# SB_TS_1_54.net
KiCad netlist of a schematic drawn in EAGLE
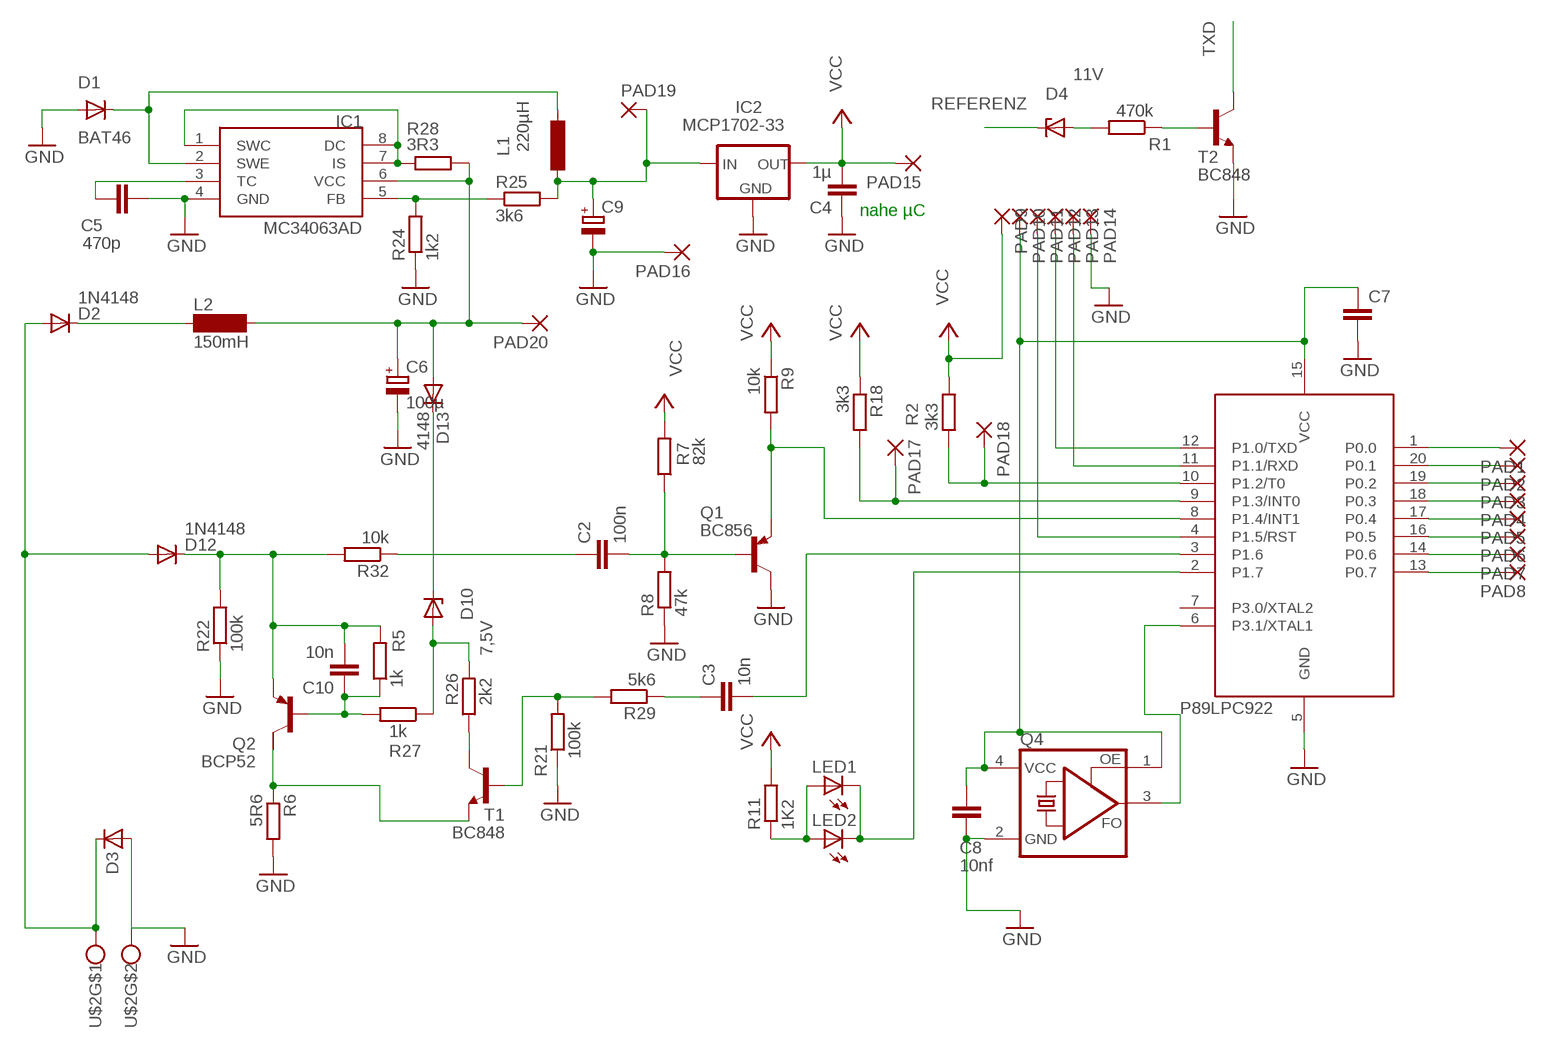
[diagram p0: schematic, sheet 1]

(export (version "E")
  (design (tool "Eeschema 10.0.6"))
  (components
    (comp (ref "C2")
      (value "100n")
      (footprint "eagle-import:C1206")
      (libsource (lib "eagle-import") (part "C-EUC1206"))
    )
    (comp (ref "C3")
      (value "10n")
      (footprint "eagle-import:C1206")
      (libsource (lib "eagle-import") (part "C-EUC1206"))
    )
    (comp (ref "C4")
      (value "1µ")
      (footprint "eagle-import:C1206")
      (libsource (lib "eagle-import") (part "C-EUC1206"))
    )
    (comp (ref "C5")
      (value "470p")
      (footprint "eagle-import:C1206")
      (libsource (lib "eagle-import") (part "C-EUC1206"))
    )
    (comp (ref "C6")
      (value "100µ")
      (footprint "eagle-import:SANYO-OSCON_SMD_C6")
      (libsource (lib "eagle-import") (part "CPOL-EUSANYO_SMD_C6"))
    )
    (comp (ref "C7")
      (value "C-EUC1206")
      (footprint "eagle-import:C1206")
      (libsource (lib "eagle-import") (part "C-EUC1206"))
    )
    (comp (ref "C8")
      (value "10nf")
      (footprint "eagle-import:C1206")
      (libsource (lib "eagle-import") (part "C-EUC1206"))
    )
    (comp (ref "C9")
      (value "CPOL-EUE2.5-5")
      (footprint "eagle-import:E2,5-5")
      (libsource (lib "eagle-import") (part "CPOL-EUE2.5-5"))
    )
    (comp (ref "C10")
      (value "10n")
      (footprint "eagle-import:C1206")
      (libsource (lib "eagle-import") (part "C-EUC1206"))
    )
    (comp (ref "D1")
      (value "BAT46")
      (footprint "eagle-import:MINIMELF")
      (libsource (lib "eagle-import") (part "DIODE-MINIMELF"))
    )
    (comp (ref "D2")
      (value "1N4148")
      (footprint "eagle-import:MINIMELF")
      (libsource (lib "eagle-import") (part "DIODE-MINIMELF"))
    )
    (comp (ref "D3")
      (value "SMAJ40AC")
      (footprint "eagle-import:SMB")
      (libsource (lib "eagle-import") (part "D-SMB"))
    )
    (comp (ref "D4")
      (value "11V")
      (footprint "eagle-import:MINIMELF")
      (libsource (lib "eagle-import") (part "ZPD"))
    )
    (comp (ref "D10")
      (value "7,5V")
      (footprint "eagle-import:MINIMELF")
      (libsource (lib "eagle-import") (part "ZPD"))
    )
    (comp (ref "D12")
      (value "1N4148")
      (footprint "eagle-import:MINIMELF")
      (libsource (lib "eagle-import") (part "DIODE-MINIMELF"))
    )
    (comp (ref "D13")
      (value "4148")
      (footprint "eagle-import:MINIMELF")
      (libsource (lib "eagle-import") (part "DIODE-MINIMELF"))
    )
    (comp (ref "IC1")
      (value "MC34063AD")
      (footprint "eagle-import:SOIC8")
      (libsource (lib "eagle-import") (part "MC34063AD"))
    )
    (comp (ref "IC2")
      (value "MCP1702-33")
      (footprint "eagle-import:79LXX")
      (libsource (lib "eagle-import") (part "79LXX"))
    )
    (comp (ref "L1")
      (value "220µH")
      (footprint "eagle-import:2200-11.43")
      (libsource (lib "eagle-import") (part "L-EU2200-11.43"))
    )
    (comp (ref "L2")
      (value "150mH")
      (footprint "eagle-import:SD12_1000")
      (libsource (lib "eagle-import") (part "SD12-1000"))
    )
    (comp (ref "LED1")
      (value "LEDCHIPLED_1206")
      (footprint "eagle-import:CHIPLED_1206")
      (libsource (lib "eagle-import") (part "LEDCHIPLED_1206"))
    )
    (comp (ref "LED2")
      (value "LED3MM")
      (footprint "eagle-import:LED3MM")
      (libsource (lib "eagle-import") (part "LED3MM"))
    )
    (comp (ref "PAD1")
      (value "SMD2")
      (footprint "eagle-import:SMD1,27-2,54")
      (libsource (lib "eagle-import") (part "SMD2"))
    )
    (comp (ref "PAD2")
      (value "SMD2")
      (footprint "eagle-import:SMD1,27-2,54")
      (libsource (lib "eagle-import") (part "SMD2"))
    )
    (comp (ref "PAD3")
      (value "SMD2")
      (footprint "eagle-import:SMD1,27-2,54")
      (libsource (lib "eagle-import") (part "SMD2"))
    )
    (comp (ref "PAD4")
      (value "SMD2")
      (footprint "eagle-import:SMD1,27-2,54")
      (libsource (lib "eagle-import") (part "SMD2"))
    )
    (comp (ref "PAD5")
      (value "SMD2")
      (footprint "eagle-import:SMD1,27-2,54")
      (libsource (lib "eagle-import") (part "SMD2"))
    )
    (comp (ref "PAD6")
      (value "SMD2")
      (footprint "eagle-import:SMD1,27-2,54")
      (libsource (lib "eagle-import") (part "SMD2"))
    )
    (comp (ref "PAD7")
      (value "SMD2")
      (footprint "eagle-import:SMD1,27-2,54")
      (libsource (lib "eagle-import") (part "SMD2"))
    )
    (comp (ref "PAD8")
      (value "SMD2")
      (footprint "eagle-import:SMD1,27-2,54")
      (libsource (lib "eagle-import") (part "SMD2"))
    )
    (comp (ref "PAD9")
      (value "SMD2")
      (footprint "eagle-import:SMD1,27-2,54")
      (libsource (lib "eagle-import") (part "SMD2"))
    )
    (comp (ref "PAD10")
      (value "SMD2")
      (footprint "eagle-import:SMD1,27-2,54")
      (libsource (lib "eagle-import") (part "SMD2"))
    )
    (comp (ref "PAD11")
      (value "SMD2")
      (footprint "eagle-import:SMD1,27-2,54")
      (libsource (lib "eagle-import") (part "SMD2"))
    )
    (comp (ref "PAD12")
      (value "SMD2")
      (footprint "eagle-import:SMD1,27-2,54")
      (libsource (lib "eagle-import") (part "SMD2"))
    )
    (comp (ref "PAD13")
      (value "SMD2")
      (footprint "eagle-import:SMD1,27-2,54")
      (libsource (lib "eagle-import") (part "SMD2"))
    )
    (comp (ref "PAD14")
      (value "SMD2")
      (footprint "eagle-import:SMD1,27-2,54")
      (libsource (lib "eagle-import") (part "SMD2"))
    )
    (comp (ref "PAD15")
      (value "SMD2")
      (footprint "eagle-import:SMD1,27-2,54")
      (libsource (lib "eagle-import") (part "SMD2"))
    )
    (comp (ref "PAD16")
      (value "SMD2")
      (footprint "eagle-import:SMD1,27-2,54")
      (libsource (lib "eagle-import") (part "SMD2"))
    )
    (comp (ref "PAD17")
      (value "SMD2")
      (footprint "eagle-import:SMD1,27-2,54")
      (libsource (lib "eagle-import") (part "SMD2"))
    )
    (comp (ref "PAD18")
      (value "SMD2")
      (footprint "eagle-import:SMD1,27-2,54")
      (libsource (lib "eagle-import") (part "SMD2"))
    )
    (comp (ref "PAD19")
      (value "SMD2")
      (footprint "eagle-import:SMD1,27-2,54")
      (libsource (lib "eagle-import") (part "SMD2"))
    )
    (comp (ref "PAD20")
      (value "SMD2")
      (footprint "eagle-import:SMD1,27-2,54")
      (libsource (lib "eagle-import") (part "SMD2"))
    )
    (comp (ref "Q1")
      (value "BC856")
      (footprint "eagle-import:SOT23-BEC")
      (libsource (lib "eagle-import") (part "BC856SMDALT1"))
    )
    (comp (ref "Q2")
      (value "BCP52")
      (footprint "eagle-import:SOT223")
      (libsource (lib "eagle-import") (part "FZT753SMD"))
    )
    (comp (ref "Q4")
      (value "ASFL")
      (footprint "eagle-import:ASF")
      (libsource (lib "eagle-import") (part "ASFL"))
    )
    (comp (ref "R1")
      (value "470k")
      (footprint "eagle-import:R1206")
      (libsource (lib "eagle-import") (part "R-EU_R1206"))
    )
    (comp (ref "R2")
      (value "3k3")
      (footprint "eagle-import:M1206")
      (libsource (lib "eagle-import") (part "R-EU_M1206"))
    )
    (comp (ref "R5")
      (value "1k")
      (footprint "eagle-import:R1206")
      (libsource (lib "eagle-import") (part "R-EU_R1206"))
    )
    (comp (ref "R6")
      (value "5R6")
      (footprint "eagle-import:R1206")
      (libsource (lib "eagle-import") (part "R-EU_R1206"))
    )
    (comp (ref "R7")
      (value "82k")
      (footprint "eagle-import:R1206")
      (libsource (lib "eagle-import") (part "R-EU_R1206"))
    )
    (comp (ref "R8")
      (value "47k")
      (footprint "eagle-import:M1206")
      (libsource (lib "eagle-import") (part "R-EU_M1206"))
    )
    (comp (ref "R9")
      (value "10k")
      (footprint "eagle-import:R1206")
      (libsource (lib "eagle-import") (part "R-EU_R1206"))
    )
    (comp (ref "R11")
      (value "1K2")
      (footprint "eagle-import:R1206")
      (libsource (lib "eagle-import") (part "R-EU_R1206"))
    )
    (comp (ref "R18")
      (value "3k3")
      (footprint "eagle-import:R1206")
      (libsource (lib "eagle-import") (part "R-EU_R1206"))
    )
    (comp (ref "R21")
      (value "100k")
      (footprint "eagle-import:R1206")
      (libsource (lib "eagle-import") (part "R-EU_R1206"))
    )
    (comp (ref "R22")
      (value "100k")
      (footprint "eagle-import:M1206")
      (libsource (lib "eagle-import") (part "R-EU_M1206"))
    )
    (comp (ref "R24")
      (value "1k2")
      (footprint "eagle-import:R1206")
      (libsource (lib "eagle-import") (part "R-EU_R1206"))
    )
    (comp (ref "R25")
      (value "3k6")
      (footprint "eagle-import:M1206")
      (libsource (lib "eagle-import") (part "R-EU_M1206"))
    )
    (comp (ref "R26")
      (value "2k2")
      (footprint "eagle-import:M1206")
      (libsource (lib "eagle-import") (part "R-EU_M1206"))
    )
    (comp (ref "R27")
      (value "1k")
      (footprint "eagle-import:R1206")
      (libsource (lib "eagle-import") (part "R-EU_R1206"))
    )
    (comp (ref "R28")
      (value "3R3")
      (footprint "eagle-import:M1206")
      (libsource (lib "eagle-import") (part "R-EU_M1206"))
    )
    (comp (ref "R29")
      (value "5k6")
      (footprint "eagle-import:R1206")
      (libsource (lib "eagle-import") (part "R-EU_R1206"))
    )
    (comp (ref "R32")
      (value "10k")
      (footprint "eagle-import:R1206")
      (libsource (lib "eagle-import") (part "R-EU_R1206"))
    )
    (comp (ref "T1")
      (value "BC848")
      (footprint "eagle-import:SOT23")
      (libsource (lib "eagle-import") (part "BC848"))
    )
    (comp (ref "T2")
      (value "BC848")
      (footprint "eagle-import:SOT23")
      (libsource (lib "eagle-import") (part "BC848"))
    )
    (comp (ref "U$2")
      (value "AKL059-02")
      (footprint "eagle-import:AKL3.5X2")
      (libsource (lib "eagle-import") (part "AKL059-02"))
    )
    (comp (ref "U1")
      (value "89LPC922")
      (footprint "eagle-import:DIL20")
      (libsource (lib "eagle-import") (part "89LPC922"))
    )
  )
  (nets
    (net (code "1") (name "/REFERENZ") (class "Default")
      (node (ref "D10") (pin "A") (pinfunction "A_A") (pintype "passive"))
      (node (ref "D4") (pin "C") (pinfunction "C_C") (pintype "passive"))
      (node (ref "R26") (pin "2") (pinfunction "2_2") (pintype "passive"))
      (node (ref "R27") (pin "1") (pinfunction "1_1") (pintype "passive"))
    )
    (net (code "2") (name "/TXD") (class "Default")
      (node (ref "PAD12") (pin "1") (pinfunction "P_1") (pintype "passive"))
      (node (ref "T2") (pin "3") (pinfunction "C_3") (pintype "passive"))
      (node (ref "U1") (pin "12") (pinfunction "P1.0/TXD_12") (pintype "bidirectional"))
    )
    (net (code "3") (name "GND") (class "Default")
      (node (ref "C4") (pin "1") (pinfunction "1_1") (pintype "passive"))
      (node (ref "C5") (pin "2") (pinfunction "2_2") (pintype "passive"))
      (node (ref "C6") (pin "-") (pinfunction "-_-") (pintype "passive"))
      (node (ref "C7") (pin "2") (pinfunction "2_2") (pintype "passive"))
      (node (ref "C8") (pin "2") (pinfunction "2_2") (pintype "passive"))
      (node (ref "C9") (pin "-") (pinfunction "-_-") (pintype "passive"))
      (node (ref "D1") (pin "A") (pinfunction "A_A") (pintype "passive"))
      (node (ref "D3") (pin "2") (pinfunction "A_2") (pintype "passive"))
      (node (ref "IC1") (pin "4") (pinfunction "GND_4") (pintype "passive"))
      (node (ref "IC2") (pin "GND") (pinfunction "GND_GND") (pintype "input"))
      (node (ref "PAD14") (pin "1") (pinfunction "P_1") (pintype "passive"))
      (node (ref "PAD16") (pin "1") (pinfunction "P_1") (pintype "passive"))
      (node (ref "Q1") (pin "C") (pinfunction "C_C") (pintype "passive"))
      (node (ref "Q4") (pin "2") (pinfunction "GND_2") (pintype "power_in"))
      (node (ref "R21") (pin "1") (pinfunction "1_1") (pintype "passive"))
      (node (ref "R22") (pin "1") (pinfunction "1_1") (pintype "passive"))
      (node (ref "R24") (pin "1") (pinfunction "1_1") (pintype "passive"))
      (node (ref "R6") (pin "2") (pinfunction "2_2") (pintype "passive"))
      (node (ref "R8") (pin "1") (pinfunction "1_1") (pintype "passive"))
      (node (ref "T2") (pin "2") (pinfunction "E_2") (pintype "passive"))
      (node (ref "U$2") (pin "2") (pinfunction "KL_2") (pintype "passive"))
      (node (ref "U1") (pin "5") (pinfunction "GND_5") (pintype "bidirectional"))
    )
    (net (code "4") (name "Net-(C2-Pad1)") (class "Default")
      (node (ref "C2") (pin "1") (pinfunction "1_1") (pintype "passive"))
      (node (ref "R32") (pin "1") (pinfunction "1_1") (pintype "passive"))
    )
    (net (code "5") (name "Net-(C2-Pad2)") (class "Default")
      (node (ref "C2") (pin "2") (pinfunction "2_2") (pintype "passive"))
      (node (ref "Q1") (pin "B") (pinfunction "B_B") (pintype "passive"))
      (node (ref "R7") (pin "1") (pinfunction "1_1") (pintype "passive"))
      (node (ref "R8") (pin "2") (pinfunction "2_2") (pintype "passive"))
    )
    (net (code "6") (name "Net-(C3-Pad1)") (class "Default")
      (node (ref "C3") (pin "1") (pinfunction "1_1") (pintype "passive"))
      (node (ref "R29") (pin "1") (pinfunction "1_1") (pintype "passive"))
    )
    (net (code "7") (name "Net-(D2-PadC)") (class "Default")
      (node (ref "D2") (pin "C") (pinfunction "C_C") (pintype "passive"))
      (node (ref "L2") (pin "1") (pinfunction "1_1") (pintype "passive"))
    )
    (net (code "8") (name "Net-(D3-C)") (class "Default")
      (node (ref "D12") (pin "A") (pinfunction "A_A") (pintype "passive"))
      (node (ref "D2") (pin "A") (pinfunction "A_A") (pintype "passive"))
      (node (ref "D3") (pin "1") (pinfunction "C_1") (pintype "passive"))
      (node (ref "U$2") (pin "1") (pinfunction "KL_1") (pintype "passive"))
    )
    (net (code "9") (name "Net-(D4-PadA)") (class "Default")
      (node (ref "D4") (pin "A") (pinfunction "A_A") (pintype "passive"))
      (node (ref "R1") (pin "2") (pinfunction "2_2") (pintype "passive"))
    )
    (net (code "10") (name "Net-(D10-PadC)") (class "Default")
      (node (ref "D10") (pin "C") (pinfunction "C_C") (pintype "passive"))
      (node (ref "D13") (pin "C") (pinfunction "C_C") (pintype "passive"))
    )
    (net (code "11") (name "Net-(IC1-DC)") (class "Default")
      (node (ref "IC1") (pin "1") (pinfunction "SWC_1") (pintype "passive"))
      (node (ref "IC1") (pin "7") (pinfunction "IS_7") (pintype "passive"))
      (node (ref "IC1") (pin "8") (pinfunction "DC_8") (pintype "passive"))
      (node (ref "R28") (pin "1") (pinfunction "1_1") (pintype "passive"))
    )
    (net (code "12") (name "Net-(IC1-FB)") (class "Default")
      (node (ref "IC1") (pin "5") (pinfunction "FB_5") (pintype "passive"))
      (node (ref "R24") (pin "2") (pinfunction "2_2") (pintype "passive"))
      (node (ref "R25") (pin "1") (pinfunction "1_1") (pintype "passive"))
    )
    (net (code "13") (name "Net-(IC1-SWE)") (class "Default")
      (node (ref "D1") (pin "C") (pinfunction "C_C") (pintype "passive"))
      (node (ref "IC1") (pin "2") (pinfunction "SWE_2") (pintype "passive"))
      (node (ref "L1") (pin "2") (pinfunction "2_2") (pintype "passive"))
    )
    (net (code "14") (name "Net-(IC1-TC)") (class "Default")
      (node (ref "C5") (pin "1") (pinfunction "1_1") (pintype "passive"))
      (node (ref "IC1") (pin "3") (pinfunction "TC_3") (pintype "passive"))
    )
    (net (code "15") (name "Net-(IC1-VCC)") (class "Default")
      (node (ref "C6") (pin "+") (pinfunction "+_+") (pintype "passive"))
      (node (ref "D13") (pin "A") (pinfunction "A_A") (pintype "passive"))
      (node (ref "IC1") (pin "6") (pinfunction "VCC_6") (pintype "passive"))
      (node (ref "L2") (pin "2") (pinfunction "2_2") (pintype "passive"))
      (node (ref "PAD20") (pin "1") (pinfunction "P_1") (pintype "passive"))
      (node (ref "R28") (pin "2") (pinfunction "2_2") (pintype "passive"))
    )
    (net (code "16") (name "Net-(LED1-PadA)") (class "Default")
      (node (ref "LED1") (pin "A") (pinfunction "A_A") (pintype "passive"))
      (node (ref "LED2") (pin "A") (pinfunction "A_A") (pintype "passive"))
      (node (ref "R11") (pin "1") (pinfunction "1_1") (pintype "passive"))
    )
    (net (code "17") (name "Net-(LED2-C)") (class "Default")
      (node (ref "LED1") (pin "C") (pinfunction "C_C") (pintype "passive"))
      (node (ref "LED2") (pin "K") (pinfunction "C_K") (pintype "passive"))
      (node (ref "U1") (pin "2") (pinfunction "P1.7_2") (pintype "bidirectional"))
    )
    (net (code "18") (name "Net-(PAD1-P)") (class "Default")
      (node (ref "PAD1") (pin "1") (pinfunction "P_1") (pintype "passive"))
      (node (ref "U1") (pin "1") (pinfunction "P0.0_1") (pintype "bidirectional"))
    )
    (net (code "19") (name "Net-(PAD2-P)") (class "Default")
      (node (ref "PAD2") (pin "1") (pinfunction "P_1") (pintype "passive"))
      (node (ref "U1") (pin "20") (pinfunction "P0.1_20") (pintype "bidirectional"))
    )
    (net (code "20") (name "Net-(PAD3-P)") (class "Default")
      (node (ref "PAD3") (pin "1") (pinfunction "P_1") (pintype "passive"))
      (node (ref "U1") (pin "19") (pinfunction "P0.2_19") (pintype "bidirectional"))
    )
    (net (code "21") (name "Net-(PAD4-P)") (class "Default")
      (node (ref "PAD4") (pin "1") (pinfunction "P_1") (pintype "passive"))
      (node (ref "U1") (pin "18") (pinfunction "P0.3_18") (pintype "bidirectional"))
    )
    (net (code "22") (name "Net-(PAD5-P)") (class "Default")
      (node (ref "PAD5") (pin "1") (pinfunction "P_1") (pintype "passive"))
      (node (ref "U1") (pin "17") (pinfunction "P0.4_17") (pintype "bidirectional"))
    )
    (net (code "23") (name "Net-(PAD6-P)") (class "Default")
      (node (ref "PAD6") (pin "1") (pinfunction "P_1") (pintype "passive"))
      (node (ref "U1") (pin "16") (pinfunction "P0.5_16") (pintype "bidirectional"))
    )
    (net (code "24") (name "Net-(PAD7-P)") (class "Default")
      (node (ref "PAD7") (pin "1") (pinfunction "P_1") (pintype "passive"))
      (node (ref "U1") (pin "14") (pinfunction "P0.6_14") (pintype "bidirectional"))
    )
    (net (code "25") (name "Net-(PAD8-P)") (class "Default")
      (node (ref "PAD8") (pin "1") (pinfunction "P_1") (pintype "passive"))
      (node (ref "U1") (pin "13") (pinfunction "P0.7_13") (pintype "bidirectional"))
    )
    (net (code "26") (name "Net-(PAD10-P)") (class "Default")
      (node (ref "C7") (pin "1") (pinfunction "1_1") (pintype "passive"))
      (node (ref "C8") (pin "1") (pinfunction "1_1") (pintype "passive"))
      (node (ref "PAD10") (pin "1") (pinfunction "P_1") (pintype "passive"))
      (node (ref "Q4") (pin "1") (pinfunction "OE_1") (pintype "input"))
      (node (ref "Q4") (pin "4") (pinfunction "VCC_4") (pintype "power_in"))
      (node (ref "U1") (pin "15") (pinfunction "VCC_15") (pintype "bidirectional"))
    )
    (net (code "27") (name "Net-(PAD11-P)") (class "Default")
      (node (ref "PAD11") (pin "1") (pinfunction "P_1") (pintype "passive"))
      (node (ref "U1") (pin "4") (pinfunction "P1.5/RST_4") (pintype "bidirectional"))
    )
    (net (code "28") (name "Net-(PAD13-P)") (class "Default")
      (node (ref "PAD13") (pin "1") (pinfunction "P_1") (pintype "passive"))
      (node (ref "U1") (pin "11") (pinfunction "P1.1/RXD_11") (pintype "bidirectional"))
    )
    (net (code "29") (name "Net-(PAD17-P)") (class "Default")
      (node (ref "PAD17") (pin "1") (pinfunction "P_1") (pintype "passive"))
      (node (ref "R18") (pin "2") (pinfunction "2_2") (pintype "passive"))
      (node (ref "U1") (pin "9") (pinfunction "P1.3/INT0_9") (pintype "bidirectional"))
    )
    (net (code "30") (name "Net-(PAD18-P)") (class "Default")
      (node (ref "PAD18") (pin "1") (pinfunction "P_1") (pintype "passive"))
      (node (ref "R2") (pin "2") (pinfunction "2_2") (pintype "passive"))
      (node (ref "U1") (pin "10") (pinfunction "P1.2/T0_10") (pintype "bidirectional"))
    )
    (net (code "31") (name "Net-(PAD19-P)") (class "Default")
      (node (ref "C9") (pin "+") (pinfunction "+_+") (pintype "passive"))
      (node (ref "IC2") (pin "IN") (pinfunction "IN_IN") (pintype "input"))
      (node (ref "L1") (pin "1") (pinfunction "1_1") (pintype "passive"))
      (node (ref "PAD19") (pin "1") (pinfunction "P_1") (pintype "passive"))
      (node (ref "R25") (pin "2") (pinfunction "2_2") (pintype "passive"))
    )
    (net (code "32") (name "Net-(Q2-B)") (class "Default")
      (node (ref "C10") (pin "1") (pinfunction "1_1") (pintype "passive"))
      (node (ref "Q2") (pin "1") (pinfunction "B_1") (pintype "passive"))
      (node (ref "R27") (pin "2") (pinfunction "2_2") (pintype "passive"))
      (node (ref "R5") (pin "1") (pinfunction "1_1") (pintype "passive"))
    )
    (net (code "33") (name "Net-(Q2-C)") (class "Default")
      (node (ref "Q2") (pin "2") (pinfunction "C_2") (pintype "passive"))
      (node (ref "R6") (pin "1") (pinfunction "1_1") (pintype "passive"))
      (node (ref "T1") (pin "2") (pinfunction "E_2") (pintype "passive"))
    )
    (net (code "34") (name "Net-(Q2-E)") (class "Default")
      (node (ref "C10") (pin "2") (pinfunction "2_2") (pintype "passive"))
      (node (ref "D12") (pin "C") (pinfunction "C_C") (pintype "passive"))
      (node (ref "Q2") (pin "3") (pinfunction "E_3") (pintype "passive"))
      (node (ref "R22") (pin "2") (pinfunction "2_2") (pintype "passive"))
      (node (ref "R32") (pin "2") (pinfunction "2_2") (pintype "passive"))
      (node (ref "R5") (pin "2") (pinfunction "2_2") (pintype "passive"))
    )
    (net (code "35") (name "Net-(Q4-FO)") (class "Default")
      (node (ref "Q4") (pin "3") (pinfunction "FO_3") (pintype "output"))
      (node (ref "U1") (pin "6") (pinfunction "P3.1/XTAL1_6") (pintype "bidirectional"))
    )
    (net (code "36") (name "Net-(T1-B)") (class "Default")
      (node (ref "R21") (pin "2") (pinfunction "2_2") (pintype "passive"))
      (node (ref "R29") (pin "2") (pinfunction "2_2") (pintype "passive"))
      (node (ref "T1") (pin "1") (pinfunction "B_1") (pintype "passive"))
    )
    (net (code "37") (name "Net-(T1-C)") (class "Default")
      (node (ref "R26") (pin "1") (pinfunction "1_1") (pintype "passive"))
      (node (ref "T1") (pin "3") (pinfunction "C_3") (pintype "passive"))
    )
    (net (code "38") (name "Net-(T2-B)") (class "Default")
      (node (ref "R1") (pin "1") (pinfunction "1_1") (pintype "passive"))
      (node (ref "T2") (pin "1") (pinfunction "B_1") (pintype "passive"))
    )
    (net (code "39") (name "Net-(U1-P1.4{slash}INT1)") (class "Default")
      (node (ref "Q1") (pin "E") (pinfunction "E_E") (pintype "passive"))
      (node (ref "R9") (pin "2") (pinfunction "2_2") (pintype "passive"))
      (node (ref "U1") (pin "8") (pinfunction "P1.4/INT1_8") (pintype "bidirectional"))
    )
    (net (code "40") (name "Net-(U1-P1.6)") (class "Default")
      (node (ref "C3") (pin "2") (pinfunction "2_2") (pintype "passive"))
      (node (ref "U1") (pin "3") (pinfunction "P1.6_3") (pintype "bidirectional"))
    )
    (net (code "41") (name "VCC") (class "Default")
      (node (ref "C4") (pin "2") (pinfunction "2_2") (pintype "passive"))
      (node (ref "IC2") (pin "OUT") (pinfunction "OUT_OUT") (pintype "passive"))
      (node (ref "PAD15") (pin "1") (pinfunction "P_1") (pintype "passive"))
      (node (ref "PAD9") (pin "1") (pinfunction "P_1") (pintype "passive"))
      (node (ref "R11") (pin "2") (pinfunction "2_2") (pintype "passive"))
      (node (ref "R18") (pin "1") (pinfunction "1_1") (pintype "passive"))
      (node (ref "R2") (pin "1") (pinfunction "1_1") (pintype "passive"))
      (node (ref "R7") (pin "2") (pinfunction "2_2") (pintype "passive"))
      (node (ref "R9") (pin "1") (pinfunction "1_1") (pintype "passive"))
    )
    (net (code "42") (name "unconnected-(Q2-C{slash}-Pad4)") (class "Default")
      (node (ref "Q2") (pin "4") (pinfunction "C/_4") (pintype "passive"))
    )
    (net (code "43") (name "unconnected-(U1-P3.0{slash}XTAL2-Pad7)") (class "Default")
      (node (ref "U1") (pin "7") (pinfunction "P3.0/XTAL2_7") (pintype "bidirectional"))
    )
  )
)
